# power_interface.net
KiCad netlist of a schematic drawn in Altium Designer
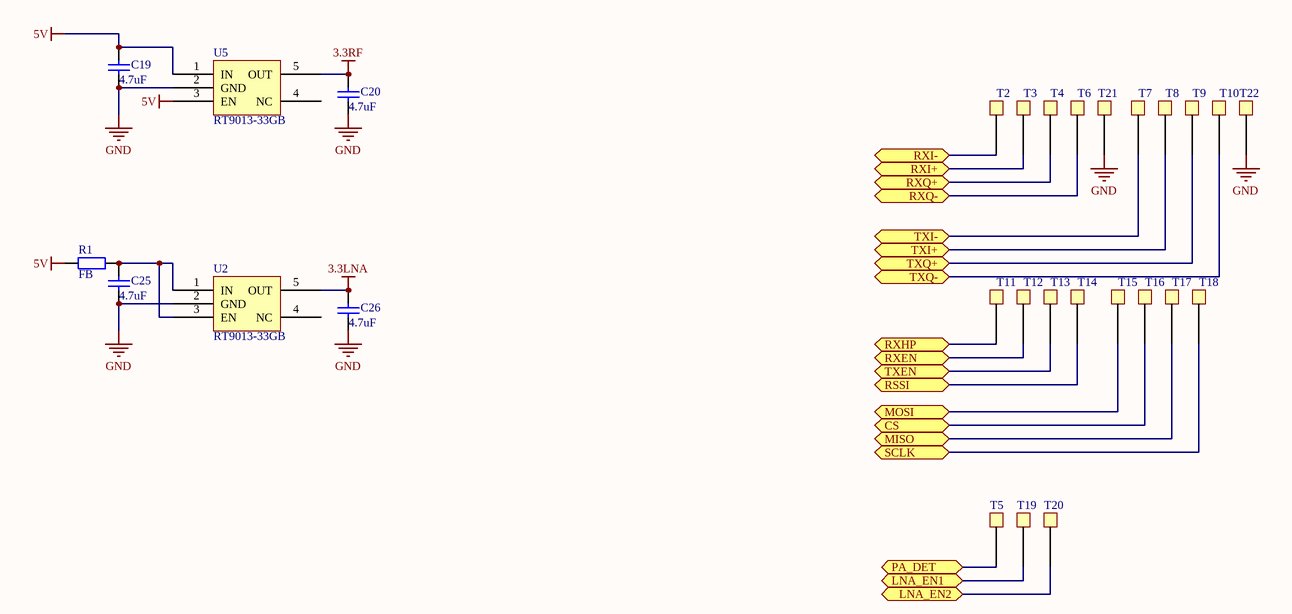
[diagram p0: power&interface.SchDoc]

(export (version "E")
  (design (tool "Eeschema 10.0.6"))
  (components
    (comp (ref "C19")
      (value "4.7uF")
      (footprint "0603")
      (description "Capacitor")
      (fields (field (name "PUBLISHER") "Altium Limited"))
      (libsource (lib "RTC6705") (part "Cap"))
    )
    (comp (ref "C20")
      (value "4.7uF")
      (footprint "0603")
      (description "Capacitor")
      (fields (field (name "PUBLISHER") "Altium Limited"))
      (libsource (lib "RTC6705") (part "Cap"))
    )
    (comp (ref "C25")
      (value "4.7uF")
      (footprint "0603")
      (description "Capacitor")
      (fields (field (name "PUBLISHER") "Altium Limited"))
      (libsource (lib "RTC6705") (part "Cap"))
    )
    (comp (ref "C26")
      (value "4.7uF")
      (footprint "0603")
      (description "Capacitor")
      (fields (field (name "PUBLISHER") "Altium Limited"))
      (libsource (lib "RTC6705") (part "Cap"))
    )
    (comp (ref "R1")
      (value "FB")
      (footprint "0402")
      (description "Resistor")
      (fields (field (name "PUBLISHER") "Altium Limited"))
      (libsource (lib "Miscellaneous Devices") (part "Res2"))
    )
    (comp (ref "T2") (value "RXI-") (footprint "TestPad - 1mm") (libsource (lib "sch") (part "TestPad")))
    (comp (ref "T3") (value "RXI-") (footprint "TestPad - 1mm") (libsource (lib "sch") (part "TestPad")))
    (comp (ref "T4") (value "RXI-") (footprint "TestPad - 1mm") (libsource (lib "sch") (part "TestPad")))
    (comp (ref "T5") (value "DET") (footprint "TestPad - 1mm") (libsource (lib "sch") (part "TestPad")))
    (comp (ref "T6") (value "RXI-") (footprint "TestPad - 1mm") (libsource (lib "sch") (part "TestPad")))
    (comp (ref "T7") (value "RXI-") (footprint "TestPad - 1mm") (libsource (lib "sch") (part "TestPad")))
    (comp (ref "T8") (value "RXI-") (footprint "TestPad - 1mm") (libsource (lib "sch") (part "TestPad")))
    (comp (ref "T9") (value "RXI-") (footprint "TestPad - 1mm") (libsource (lib "sch") (part "TestPad")))
    (comp (ref "T10") (value "RXI-") (footprint "TestPad - 1mm") (libsource (lib "sch") (part "TestPad")))
    (comp (ref "T11") (value "HP") (footprint "TestPad - 1mm") (libsource (lib "sch") (part "TestPad")))
    (comp (ref "T12") (value "RX") (footprint "TestPad - 1mm") (libsource (lib "sch") (part "TestPad")))
    (comp (ref "T13") (value "TX") (footprint "TestPad - 1mm") (libsource (lib "sch") (part "TestPad")))
    (comp (ref "T14") (value "RSSI") (footprint "TestPad - 1mm") (libsource (lib "sch") (part "TestPad")))
    (comp (ref "T15") (value "I") (footprint "TestPad - 1mm") (libsource (lib "sch") (part "TestPad")))
    (comp (ref "T16") (value "CS") (footprint "TestPad - 1mm") (libsource (lib "sch") (part "TestPad")))
    (comp (ref "T17") (value "O") (footprint "TestPad - 1mm") (libsource (lib "sch") (part "TestPad")))
    (comp (ref "T18") (value "C") (footprint "TestPad - 1mm") (libsource (lib "sch") (part "TestPad")))
    (comp (ref "T19") (value "L1") (footprint "TestPad - 1mm") (libsource (lib "sch") (part "TestPad")))
    (comp (ref "T20") (value "L2") (footprint "TestPad - 1mm") (libsource (lib "sch") (part "TestPad")))
    (comp (ref "T21") (value "VDET") (footprint "TestPad - 1mm") (libsource (lib "sch") (part "TestPad")))
    (comp (ref "T22") (value "VDET") (footprint "TestPad - 1mm") (libsource (lib "sch") (part "TestPad")))
    (comp (ref "U2") (value "RT9013-33GB") (footprint "SOT23-5") (libsource (lib "RTC6705") (part "LP5907")))
    (comp (ref "U5") (value "RT9013-33GB") (footprint "SOT23-5") (libsource (lib "RTC6705") (part "LP5907")))
  )
  (nets
    (net (code "1") (name "/CS") (class "Default")
      (node (ref "T16") (pin "1") (pinfunction "3_1") (pintype "passive"))
    )
    (net (code "2") (name "/LNA_EN1") (class "Default")
      (node (ref "T19") (pin "1") (pinfunction "3_1") (pintype "passive"))
    )
    (net (code "3") (name "/LNA_EN2") (class "Default")
      (node (ref "T20") (pin "1") (pinfunction "3_1") (pintype "passive"))
    )
    (net (code "4") (name "/MISO") (class "Default")
      (node (ref "T17") (pin "1") (pinfunction "3_1") (pintype "passive"))
    )
    (net (code "5") (name "/MOSI") (class "Default")
      (node (ref "T15") (pin "1") (pinfunction "3_1") (pintype "passive"))
    )
    (net (code "6") (name "/PA_DET") (class "Default")
      (node (ref "T5") (pin "1") (pinfunction "3_1") (pintype "passive"))
    )
    (net (code "7") (name "/RSSI") (class "Default")
      (node (ref "T14") (pin "1") (pinfunction "3_1") (pintype "passive"))
    )
    (net (code "8") (name "/RXEN") (class "Default")
      (node (ref "T12") (pin "1") (pinfunction "3_1") (pintype "passive"))
    )
    (net (code "9") (name "/RXHP") (class "Default")
      (node (ref "T11") (pin "1") (pinfunction "3_1") (pintype "passive"))
    )
    (net (code "10") (name "/RXI+") (class "Default")
      (node (ref "T3") (pin "1") (pinfunction "3_1") (pintype "passive"))
    )
    (net (code "11") (name "/RXI-") (class "Default")
      (node (ref "T2") (pin "1") (pinfunction "3_1") (pintype "passive"))
    )
    (net (code "12") (name "/RXQ+") (class "Default")
      (node (ref "T4") (pin "1") (pinfunction "3_1") (pintype "passive"))
    )
    (net (code "13") (name "/RXQ-") (class "Default")
      (node (ref "T6") (pin "1") (pinfunction "3_1") (pintype "passive"))
    )
    (net (code "14") (name "/SCLK") (class "Default")
      (node (ref "T18") (pin "1") (pinfunction "3_1") (pintype "passive"))
    )
    (net (code "15") (name "/TXEN") (class "Default")
      (node (ref "T13") (pin "1") (pinfunction "3_1") (pintype "passive"))
    )
    (net (code "16") (name "/TXI+") (class "Default")
      (node (ref "T8") (pin "1") (pinfunction "3_1") (pintype "passive"))
    )
    (net (code "17") (name "/TXI-") (class "Default")
      (node (ref "T7") (pin "1") (pinfunction "3_1") (pintype "passive"))
    )
    (net (code "18") (name "/TXQ+") (class "Default")
      (node (ref "T9") (pin "1") (pinfunction "3_1") (pintype "passive"))
    )
    (net (code "19") (name "/TXQ-") (class "Default")
      (node (ref "T10") (pin "1") (pinfunction "3_1") (pintype "passive"))
    )
    (net (code "20") (name "3.3LNA") (class "Default")
      (node (ref "C26") (pin "2") (pinfunction "2_2") (pintype "passive"))
      (node (ref "U2") (pin "5") (pinfunction "OUT_5") (pintype "passive"))
    )
    (net (code "21") (name "3.3RF") (class "Default")
      (node (ref "C20") (pin "2") (pinfunction "2_2") (pintype "passive"))
      (node (ref "U5") (pin "5") (pinfunction "OUT_5") (pintype "passive"))
    )
    (net (code "22") (name "5V") (class "Default")
      (node (ref "C19") (pin "2") (pinfunction "2_2") (pintype "passive"))
      (node (ref "R1") (pin "2") (pinfunction "2_2") (pintype "passive"))
      (node (ref "U5") (pin "1") (pinfunction "IN_1") (pintype "passive"))
      (node (ref "U5") (pin "3") (pinfunction "EN_3") (pintype "passive"))
    )
    (net (code "23") (name "GND") (class "Default")
      (node (ref "C19") (pin "1") (pinfunction "1_1") (pintype "passive"))
      (node (ref "C20") (pin "1") (pinfunction "1_1") (pintype "passive"))
      (node (ref "C25") (pin "1") (pinfunction "1_1") (pintype "passive"))
      (node (ref "C26") (pin "1") (pinfunction "1_1") (pintype "passive"))
      (node (ref "T21") (pin "1") (pinfunction "3_1") (pintype "passive"))
      (node (ref "T22") (pin "1") (pinfunction "3_1") (pintype "passive"))
      (node (ref "U2") (pin "2") (pinfunction "GND_2") (pintype "passive"))
      (node (ref "U5") (pin "2") (pinfunction "GND_2") (pintype "passive"))
    )
    (net (code "24") (name "Net-(U2-EN)") (class "Default")
      (node (ref "C25") (pin "2") (pinfunction "2_2") (pintype "passive"))
      (node (ref "R1") (pin "1") (pinfunction "1_1") (pintype "passive"))
      (node (ref "U2") (pin "1") (pinfunction "IN_1") (pintype "passive"))
      (node (ref "U2") (pin "3") (pinfunction "EN_3") (pintype "passive"))
    )
    (net (code "25") (name "unconnected-(U2-NC-Pad4)") (class "Default")
      (node (ref "U2") (pin "4") (pinfunction "NC_4") (pintype "passive"))
    )
    (net (code "26") (name "unconnected-(U5-NC-Pad4)") (class "Default")
      (node (ref "U5") (pin "4") (pinfunction "NC_4") (pintype "passive"))
    )
  )
)
